# isoDebug.net
KiCad netlist of a schematic drawn in Altium Designer
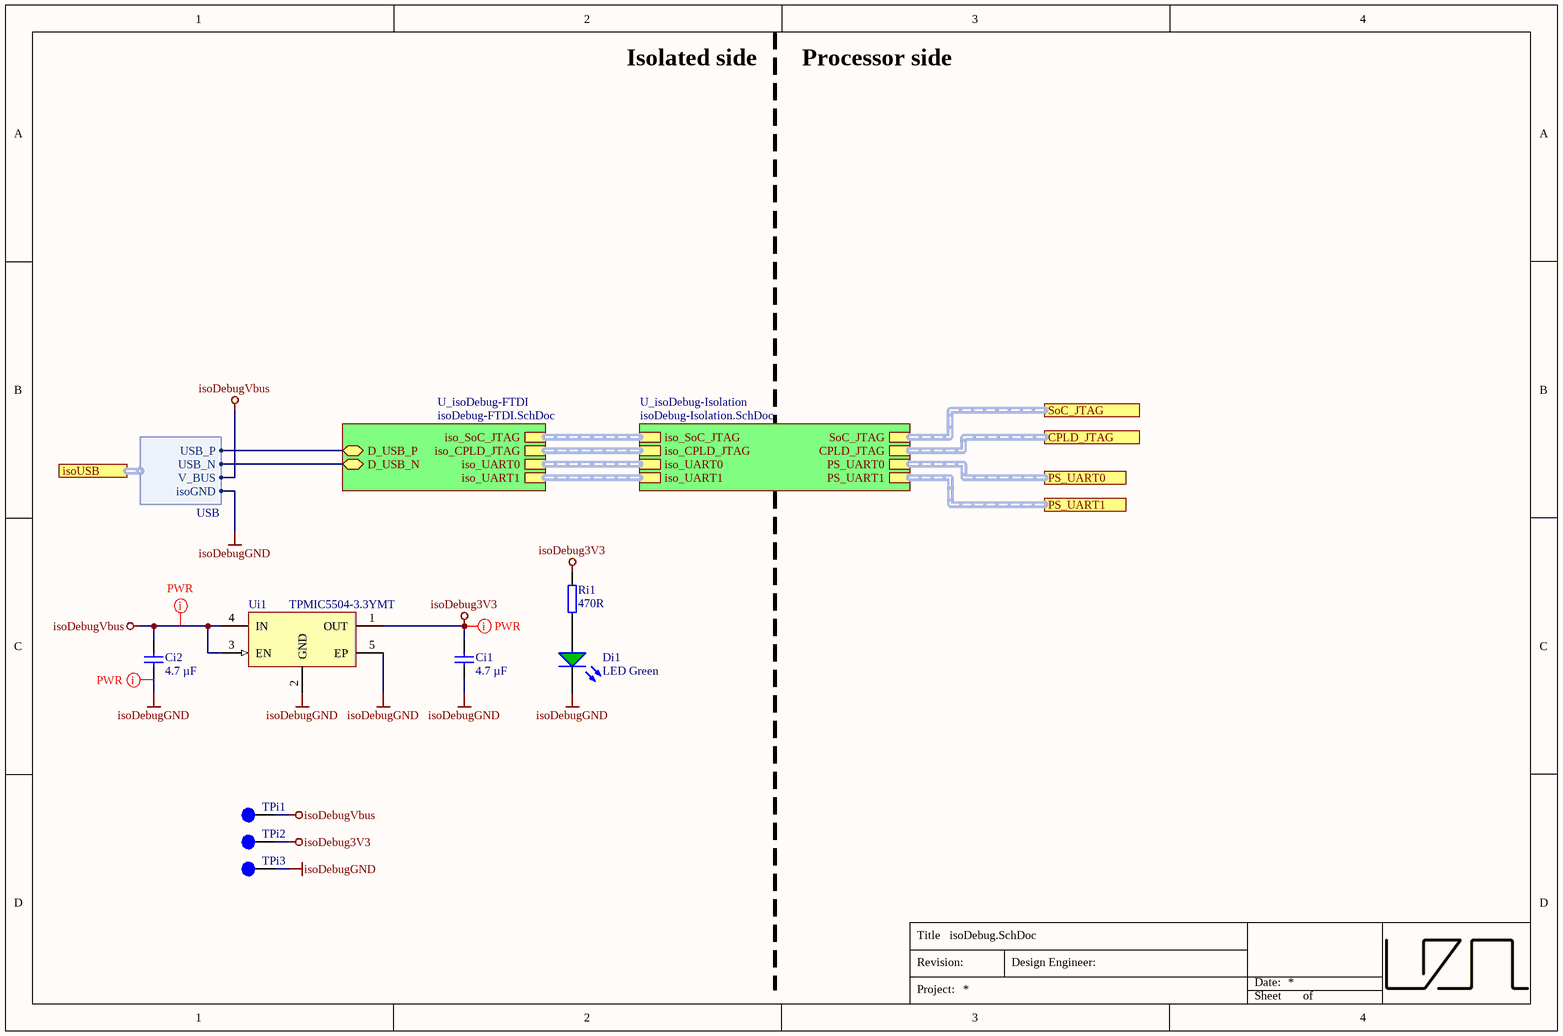
[diagram p0: isoDebug.SchDoc]

(export (version "E")
  (design (tool "Eeschema 10.0.6"))
  (components
    (comp (ref "Ci1")
      (value "4.7 µF")
      (footprint "C_0603_TE")
      (description "Generic capacitor")
      (fields
        (field (name "MANUFACTURER PART NUMBER") "UZgen_C_0603_4.7uF_16V_X5R")
        (field (name "MANUFACTURER") "UZgen")
        (field (name "CREATED FROM") "MGeier")
      )
      (libsource (lib "user") (part "CAP-NP"))
    )
    (comp (ref "Ci2")
      (value "4.7 µF")
      (footprint "C_0603_TE")
      (description "Generic capacitor")
      (fields
        (field (name "MANUFACTURER PART NUMBER") "UZgen_C_0603_4.7uF_16V_X5R")
        (field (name "MANUFACTURER") "UZgen")
        (field (name "CREATED FROM") "MGeier")
      )
      (libsource (lib "user") (part "CAP-NP"))
    )
    (comp (ref "Di1")
      (value "LED Green")
      (footprint "WL-SMCW_0603")
      (description "Standard LEDs - SMD 0603 green")
      (fields
        (field (name "MANUFACTURER PART NUMBER") "UZgen_LED_0603_Green")
        (field (name "MANUFACTURER") "UZgen")
        (field (name "CREATED FROM") "UZgenTool")
      )
      (libsource (lib "user") (part "LED_Green"))
    )
    (comp (ref "Ri1")
      (value "470R")
      (footprint "R_0603_TE")
      (description "Generic resistor")
      (fields
        (field (name "MANUFACTURER PART NUMBER") "UZgen_R_0603_470R")
        (field (name "MANUFACTURER") "UZgen")
        (field (name "CREATED FROM") "UZgenTool")
      )
      (libsource (lib "user") (part "RES"))
    )
    (comp (ref "TPi1")
      (value "Testpoint 1mm")
      (footprint "TP_1mm")
      (fields
        (field (name "MANUFACTURER PART NUMBER") "NULL")
        (field (name "CREATED") "2018_06_25_AGeiger")
        (field (name "CREATED FROM") "AGeiger")
      )
      (libsource (lib "user") (part "TP_1mm"))
    )
    (comp (ref "TPi2")
      (value "Testpoint 1mm")
      (footprint "TP_1mm")
      (fields
        (field (name "MANUFACTURER PART NUMBER") "NULL")
        (field (name "CREATED") "2018_06_25_AGeiger")
        (field (name "CREATED FROM") "AGeiger")
      )
      (libsource (lib "user") (part "TP_1mm"))
    )
    (comp (ref "TPi3")
      (value "Testpoint 1mm")
      (footprint "TP_1mm")
      (fields
        (field (name "MANUFACTURER PART NUMBER") "NULL")
        (field (name "CREATED") "2018_06_25_AGeiger")
        (field (name "CREATED FROM") "AGeiger")
      )
      (libsource (lib "user") (part "TP_1mm"))
    )
    (comp (ref "Ui1")
      (value "TPMIC5504-3.3YMT")
      (footprint "DFN-4-EP")
      (description "DFN-4-EP(1x1) Linear Voltage Regulators (LDO) ROHS")
      (fields
        (field (name "MANUFACTURER") "TECH PUBLIC")
        (field (name "LCSC PART NUMBER") "C3021135")
        (field (name "CREATED FROM") "AGeiger")
      )
      (libsource (lib "user") (part "TPMIC5504-3.3YMT"))
    )
  )
  (nets
    (net (code "17") (name "Net-(Di1-A)") (class "Default")
      (node (ref "Di1") (pin "2") (pinfunction "A_2") (pintype "passive"))
      (node (ref "Ri1") (pin "1") (pinfunction "1_1") (pintype "passive"))
    )
    (net (code "18") (name "isoDebug3V3") (class "Default")
      (node (ref "Ci1") (pin "2") (pinfunction "2_2") (pintype "passive"))
      (node (ref "Ri1") (pin "2") (pinfunction "2_2") (pintype "passive"))
      (node (ref "TPi2") (pin "1") (pintype "passive"))
      (node (ref "Ui1") (pin "1") (pinfunction "OUT_1") (pintype "power_in"))
    )
    (net (code "19") (name "isoDebugGND") (class "Default")
      (node (ref "Ci1") (pin "1") (pinfunction "1_1") (pintype "passive"))
      (node (ref "Ci2") (pin "1") (pinfunction "1_1") (pintype "passive"))
      (node (ref "Di1") (pin "1") (pinfunction "K_1") (pintype "passive"))
      (node (ref "TPi3") (pin "1") (pintype "passive"))
      (node (ref "Ui1") (pin "2") (pinfunction "GND_2") (pintype "power_in"))
      (node (ref "Ui1") (pin "5") (pinfunction "EP_5") (pintype "power_in"))
    )
    (net (code "20") (name "isoDebugVbus") (class "Default")
      (node (ref "Ci2") (pin "2") (pinfunction "2_2") (pintype "passive"))
      (node (ref "TPi1") (pin "1") (pintype "passive"))
      (node (ref "Ui1") (pin "3") (pinfunction "EN_3") (pintype "input"))
      (node (ref "Ui1") (pin "4") (pinfunction "IN_4") (pintype "power_in"))
    )
  )
)
